# RTM_SFP_TOP.net
KiCad netlist of a schematic drawn in Altium Designer
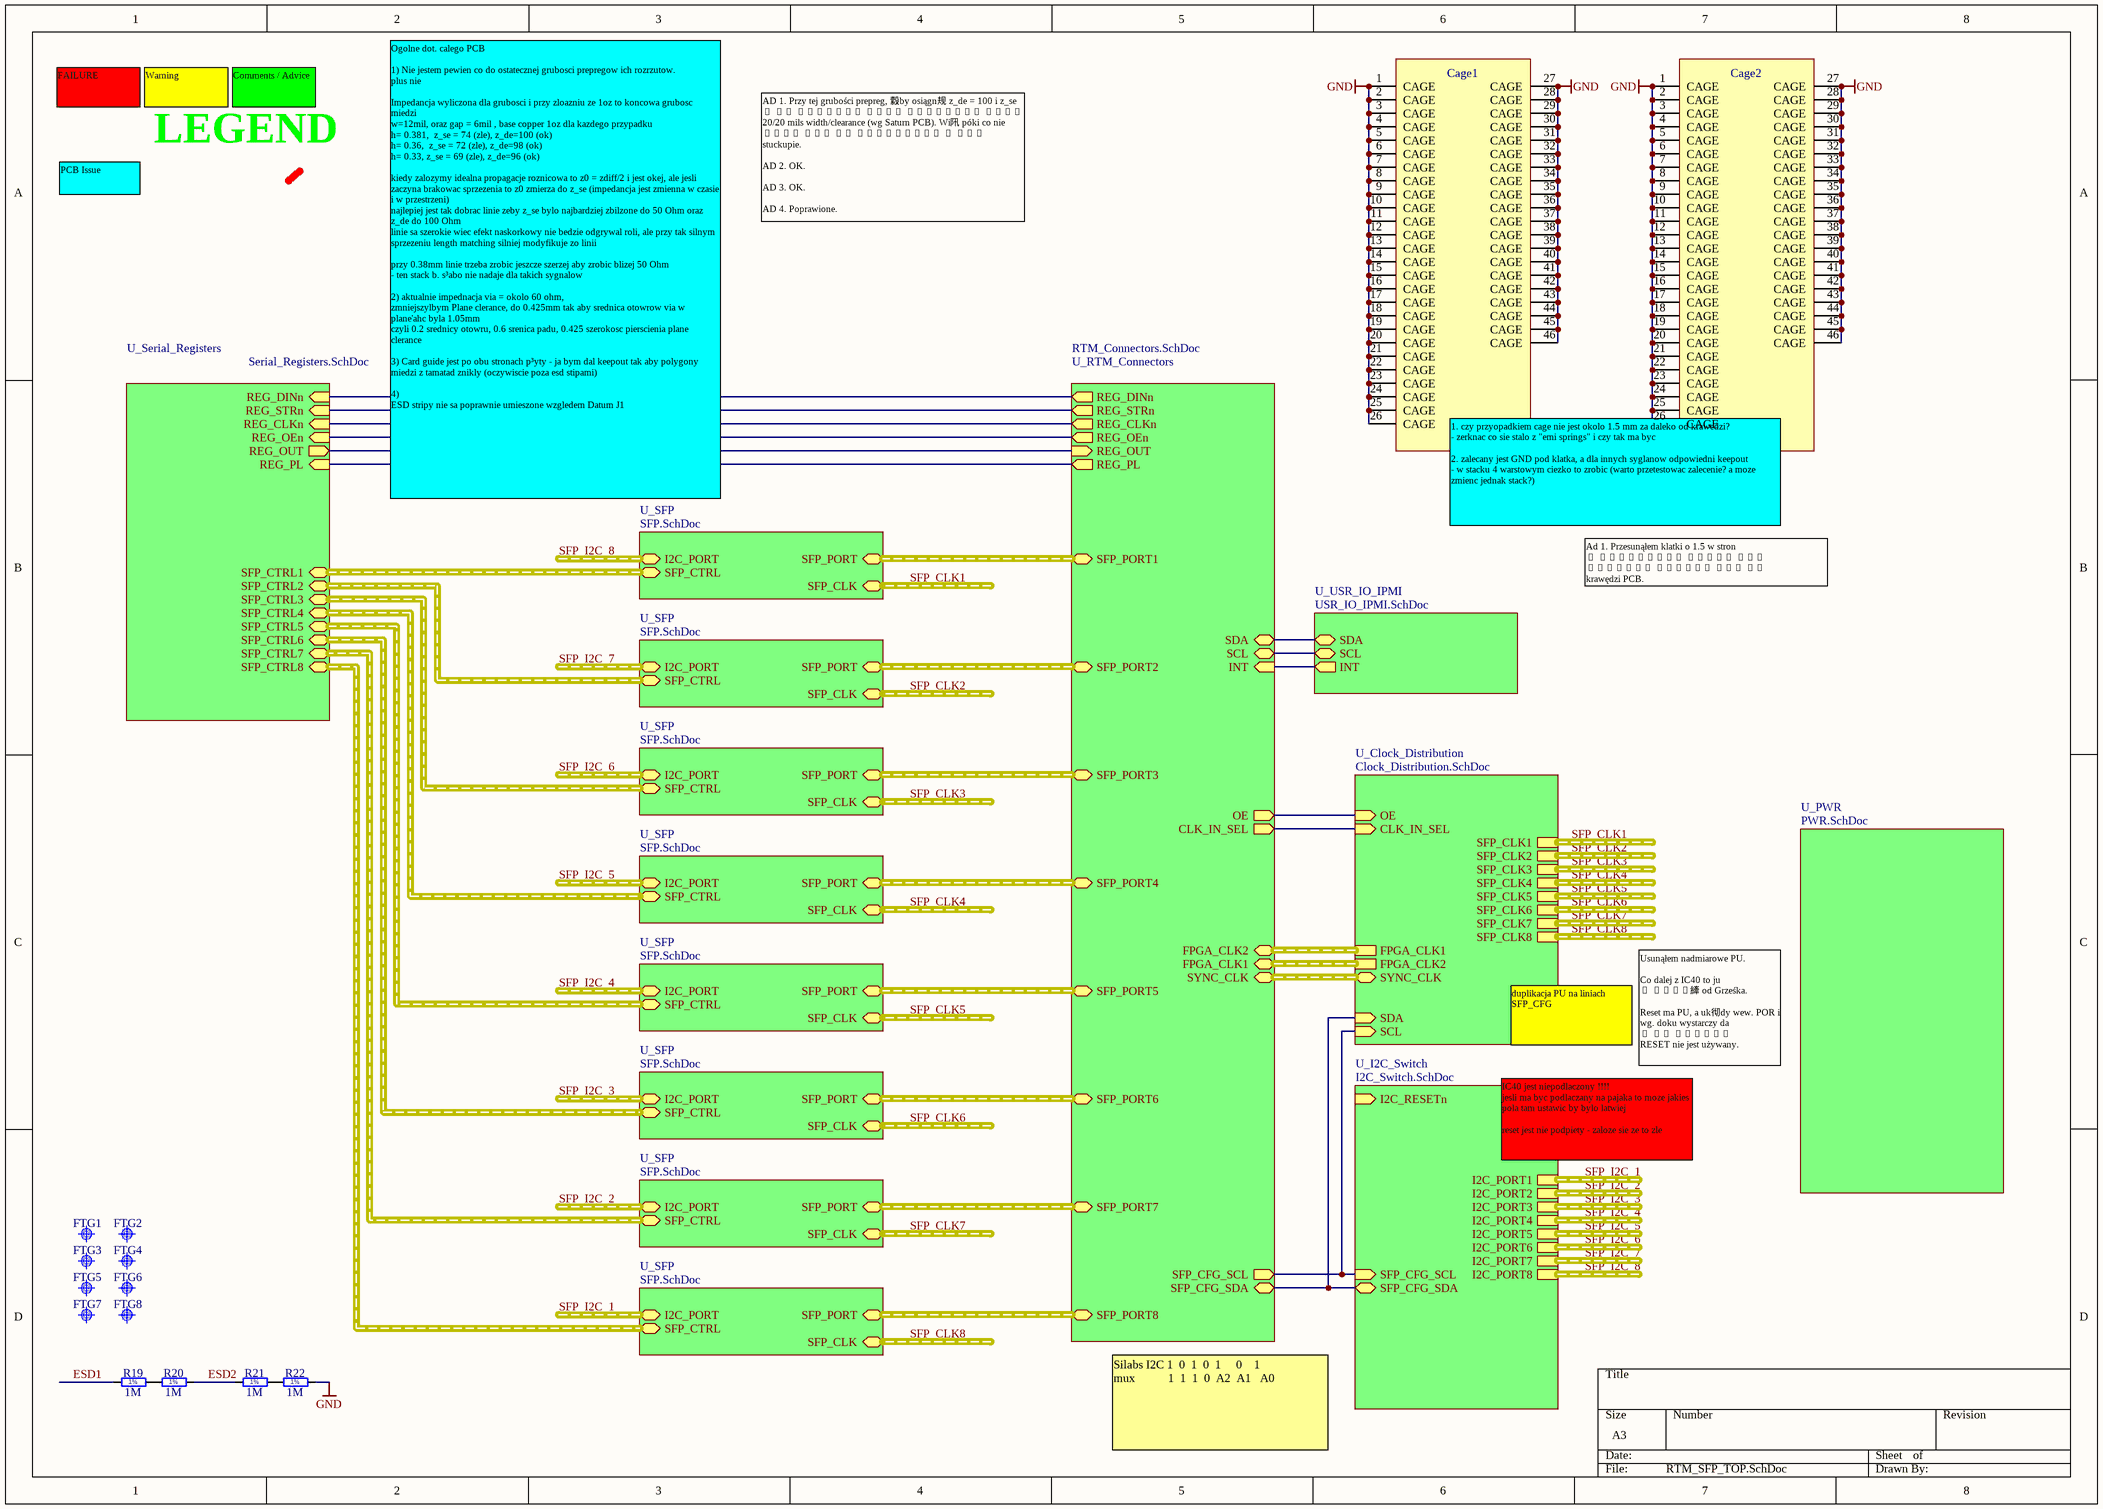
[diagram p0: RTM_SFP_TOP.SchDoc]

(export (version "E")
  (design (tool "Eeschema 10.0.6"))
  (components
    (comp (ref "Cage1")
      (value "SFP+")
      (footprint "TYCO_2007132-1")
      (description "SFP+  1x4 Cage (46 Pins)")
      (fields
        (field (name "PART NUMBER") "TYCO_2007132-1")
        (field (name "MANUFACTURER") "TYCO ELECTRONICS")
        (field (name "AUTHOR") "CERN DEM JLC")
      )
      (libsource (lib "Connectors") (part "SFP+ 1x4 Cage (46Pins)"))
    )
    (comp (ref "Cage2")
      (value "SFP+")
      (footprint "TYCO_2007132-1")
      (description "SFP+  1x4 Cage (46 Pins)")
      (fields
        (field (name "PART NUMBER") "TYCO_2007132-1")
        (field (name "MANUFACTURER") "TYCO ELECTRONICS")
        (field (name "AUTHOR") "CERN DEM JLC")
      )
      (libsource (lib "Connectors") (part "SFP+ 1x4 Cage (46Pins)"))
    )
    (comp (ref "FTG1")
      (value "Use only in PCB")
      (footprint "FIDUCIAL_TOP_S100-200")
      (description "Fiducial Target")
      (fields (field (name "PART NUMBER") "FIDUCIAL_TARGET_S100-200") (field (name "AUTHOR") "CERN DEM JLC"))
      (libsource (lib "Eletro-mechanical") (part "Fiducial Target"))
    )
    (comp (ref "FTG2")
      (value "Use only in PCB")
      (footprint "FIDUCIAL_TOP_C100-200")
      (description "Fiducial Target")
      (fields (field (name "PART NUMBER") "FIDUCIAL_TARGET_C100-200") (field (name "AUTHOR") "CERN DEM JLC"))
      (libsource (lib "Eletro-mechanical") (part "Fiducial Target"))
    )
    (comp (ref "FTG3")
      (value "Use only in PCB")
      (footprint "FIDUCIAL_TOP_S100-200")
      (description "Fiducial Target")
      (fields (field (name "PART NUMBER") "FIDUCIAL_TARGET_S100-200") (field (name "AUTHOR") "CERN DEM JLC"))
      (libsource (lib "Eletro-mechanical") (part "Fiducial Target"))
    )
    (comp (ref "FTG4")
      (value "Use only in PCB")
      (footprint "FIDUCIAL_TOP_C100-200")
      (description "Fiducial Target")
      (fields (field (name "PART NUMBER") "FIDUCIAL_TARGET_C100-200") (field (name "AUTHOR") "CERN DEM JLC"))
      (libsource (lib "Eletro-mechanical") (part "Fiducial Target"))
    )
    (comp (ref "FTG5")
      (value "Use only in PCB")
      (footprint "FIDUCIAL_TOP_S100-200")
      (description "Fiducial Target")
      (fields (field (name "PART NUMBER") "FIDUCIAL_TARGET_S100-200") (field (name "AUTHOR") "CERN DEM JLC"))
      (libsource (lib "Eletro-mechanical") (part "Fiducial Target"))
    )
    (comp (ref "FTG6")
      (value "Use only in PCB")
      (footprint "FIDUCIAL_TOP_C100-200")
      (description "Fiducial Target")
      (fields (field (name "PART NUMBER") "FIDUCIAL_TARGET_C100-200") (field (name "AUTHOR") "CERN DEM JLC"))
      (libsource (lib "Eletro-mechanical") (part "Fiducial Target"))
    )
    (comp (ref "FTG7")
      (value "Use only in PCB")
      (footprint "FIDUCIAL_TOP_S100-200")
      (description "Fiducial Target")
      (fields (field (name "PART NUMBER") "FIDUCIAL_TARGET_S100-200") (field (name "AUTHOR") "CERN DEM JLC"))
      (libsource (lib "Eletro-mechanical") (part "Fiducial Target"))
    )
    (comp (ref "FTG8")
      (value "Use only in PCB")
      (footprint "FIDUCIAL_TOP_C100-200")
      (description "Fiducial Target")
      (fields (field (name "PART NUMBER") "FIDUCIAL_TARGET_C100-200") (field (name "AUTHOR") "CERN DEM JLC"))
      (libsource (lib "Eletro-mechanical") (part "Fiducial Target"))
    )
    (comp (ref "R19")
      (value "1M")
      (footprint "RESC3216X65N")
      (description "Resistor - 1%")
      (fields
        (field (name "PART NUMBER") "R1206_1M_1%_0.25W_100PPM")
        (field (name "POWER") "0.25W")
        (field (name "AUTHOR") "CERN DEM JLC")
      )
      (libsource (lib "Resistors") (part "Resistor - 1%"))
    )
    (comp (ref "R20")
      (value "1M")
      (footprint "RESC3216X65N")
      (description "Resistor - 1%")
      (fields
        (field (name "PART NUMBER") "R1206_1M_1%_0.25W_100PPM")
        (field (name "POWER") "0.25W")
        (field (name "AUTHOR") "CERN DEM JLC")
      )
      (libsource (lib "Resistors") (part "Resistor - 1%"))
    )
    (comp (ref "R21")
      (value "1M")
      (footprint "RESC3216X65N")
      (description "Resistor - 1%")
      (fields
        (field (name "PART NUMBER") "R1206_1M_1%_0.25W_100PPM")
        (field (name "POWER") "0.25W")
        (field (name "AUTHOR") "CERN DEM JLC")
      )
      (libsource (lib "Resistors") (part "Resistor - 1%"))
    )
    (comp (ref "R22")
      (value "1M")
      (footprint "RESC3216X65N")
      (description "Resistor - 1%")
      (fields
        (field (name "PART NUMBER") "R1206_1M_1%_0.25W_100PPM")
        (field (name "POWER") "0.25W")
        (field (name "AUTHOR") "CERN DEM JLC")
      )
      (libsource (lib "Resistors") (part "Resistor - 1%"))
    )
  )
  (nets
    (net (code "18") (name "/ESD1") (class "Default")
      (node (ref "R19") (pin "1") (pinfunction "1_1") (pintype "passive"))
    )
    (net (code "19") (name "/ESD2") (class "Default")
      (node (ref "R20") (pin "2") (pinfunction "2_2") (pintype "passive"))
      (node (ref "R21") (pin "1") (pinfunction "1_1") (pintype "passive"))
    )
    (net (code "69") (name "GND") (class "Default")
      (node (ref "Cage1") (pin "1") (pinfunction "CAGE_1") (pintype "power_in"))
      (node (ref "Cage1") (pin "10") (pinfunction "CAGE_10") (pintype "power_in"))
      (node (ref "Cage1") (pin "11") (pinfunction "CAGE_11") (pintype "power_in"))
      (node (ref "Cage1") (pin "12") (pinfunction "CAGE_12") (pintype "power_in"))
      (node (ref "Cage1") (pin "13") (pinfunction "CAGE_13") (pintype "power_in"))
      (node (ref "Cage1") (pin "14") (pinfunction "CAGE_14") (pintype "power_in"))
      (node (ref "Cage1") (pin "15") (pinfunction "CAGE_15") (pintype "power_in"))
      (node (ref "Cage1") (pin "16") (pinfunction "CAGE_16") (pintype "power_in"))
      (node (ref "Cage1") (pin "17") (pinfunction "CAGE_17") (pintype "power_in"))
      (node (ref "Cage1") (pin "18") (pinfunction "CAGE_18") (pintype "power_in"))
      (node (ref "Cage1") (pin "19") (pinfunction "CAGE_19") (pintype "power_in"))
      (node (ref "Cage1") (pin "2") (pinfunction "CAGE_2") (pintype "power_in"))
      (node (ref "Cage1") (pin "20") (pinfunction "CAGE_20") (pintype "power_in"))
      (node (ref "Cage1") (pin "21") (pinfunction "CAGE_21") (pintype "power_in"))
      (node (ref "Cage1") (pin "22") (pinfunction "CAGE_22") (pintype "power_in"))
      (node (ref "Cage1") (pin "23") (pinfunction "CAGE_23") (pintype "power_in"))
      (node (ref "Cage1") (pin "24") (pinfunction "CAGE_24") (pintype "power_in"))
      (node (ref "Cage1") (pin "25") (pinfunction "CAGE_25") (pintype "power_in"))
      (node (ref "Cage1") (pin "26") (pinfunction "CAGE_26") (pintype "power_in"))
      (node (ref "Cage1") (pin "27") (pinfunction "CAGE_27") (pintype "power_in"))
      (node (ref "Cage1") (pin "28") (pinfunction "CAGE_28") (pintype "power_in"))
      (node (ref "Cage1") (pin "29") (pinfunction "CAGE_29") (pintype "power_in"))
      (node (ref "Cage1") (pin "3") (pinfunction "CAGE_3") (pintype "power_in"))
      (node (ref "Cage1") (pin "30") (pinfunction "CAGE_30") (pintype "power_in"))
      (node (ref "Cage1") (pin "31") (pinfunction "CAGE_31") (pintype "power_in"))
      (node (ref "Cage1") (pin "32") (pinfunction "CAGE_32") (pintype "power_in"))
      (node (ref "Cage1") (pin "33") (pinfunction "CAGE_33") (pintype "power_in"))
      (node (ref "Cage1") (pin "34") (pinfunction "CAGE_34") (pintype "power_in"))
      (node (ref "Cage1") (pin "35") (pinfunction "CAGE_35") (pintype "power_in"))
      (node (ref "Cage1") (pin "36") (pinfunction "CAGE_36") (pintype "power_in"))
      (node (ref "Cage1") (pin "37") (pinfunction "CAGE_37") (pintype "power_in"))
      (node (ref "Cage1") (pin "38") (pinfunction "CAGE_38") (pintype "power_in"))
      (node (ref "Cage1") (pin "39") (pinfunction "CAGE_39") (pintype "power_in"))
      (node (ref "Cage1") (pin "4") (pinfunction "CAGE_4") (pintype "power_in"))
      (node (ref "Cage1") (pin "40") (pinfunction "CAGE_40") (pintype "power_in"))
      (node (ref "Cage1") (pin "41") (pinfunction "CAGE_41") (pintype "power_in"))
      (node (ref "Cage1") (pin "42") (pinfunction "CAGE_42") (pintype "power_in"))
      (node (ref "Cage1") (pin "43") (pinfunction "CAGE_43") (pintype "power_in"))
      (node (ref "Cage1") (pin "44") (pinfunction "CAGE_44") (pintype "power_in"))
      (node (ref "Cage1") (pin "45") (pinfunction "CAGE_45") (pintype "power_in"))
      (node (ref "Cage1") (pin "46") (pinfunction "CAGE_46") (pintype "power_in"))
      (node (ref "Cage1") (pin "5") (pinfunction "CAGE_5") (pintype "power_in"))
      (node (ref "Cage1") (pin "6") (pinfunction "CAGE_6") (pintype "power_in"))
      (node (ref "Cage1") (pin "7") (pinfunction "CAGE_7") (pintype "power_in"))
      (node (ref "Cage1") (pin "8") (pinfunction "CAGE_8") (pintype "power_in"))
      (node (ref "Cage1") (pin "9") (pinfunction "CAGE_9") (pintype "power_in"))
      (node (ref "Cage2") (pin "1") (pinfunction "CAGE_1") (pintype "power_in"))
      (node (ref "Cage2") (pin "10") (pinfunction "CAGE_10") (pintype "power_in"))
      (node (ref "Cage2") (pin "11") (pinfunction "CAGE_11") (pintype "power_in"))
      (node (ref "Cage2") (pin "12") (pinfunction "CAGE_12") (pintype "power_in"))
      (node (ref "Cage2") (pin "13") (pinfunction "CAGE_13") (pintype "power_in"))
      (node (ref "Cage2") (pin "14") (pinfunction "CAGE_14") (pintype "power_in"))
      (node (ref "Cage2") (pin "15") (pinfunction "CAGE_15") (pintype "power_in"))
      (node (ref "Cage2") (pin "16") (pinfunction "CAGE_16") (pintype "power_in"))
      (node (ref "Cage2") (pin "17") (pinfunction "CAGE_17") (pintype "power_in"))
      (node (ref "Cage2") (pin "18") (pinfunction "CAGE_18") (pintype "power_in"))
      (node (ref "Cage2") (pin "19") (pinfunction "CAGE_19") (pintype "power_in"))
      (node (ref "Cage2") (pin "2") (pinfunction "CAGE_2") (pintype "power_in"))
      (node (ref "Cage2") (pin "20") (pinfunction "CAGE_20") (pintype "power_in"))
      (node (ref "Cage2") (pin "21") (pinfunction "CAGE_21") (pintype "power_in"))
      (node (ref "Cage2") (pin "22") (pinfunction "CAGE_22") (pintype "power_in"))
      (node (ref "Cage2") (pin "23") (pinfunction "CAGE_23") (pintype "power_in"))
      (node (ref "Cage2") (pin "24") (pinfunction "CAGE_24") (pintype "power_in"))
      (node (ref "Cage2") (pin "25") (pinfunction "CAGE_25") (pintype "power_in"))
      (node (ref "Cage2") (pin "26") (pinfunction "CAGE_26") (pintype "power_in"))
      (node (ref "Cage2") (pin "27") (pinfunction "CAGE_27") (pintype "power_in"))
      (node (ref "Cage2") (pin "28") (pinfunction "CAGE_28") (pintype "power_in"))
      (node (ref "Cage2") (pin "29") (pinfunction "CAGE_29") (pintype "power_in"))
      (node (ref "Cage2") (pin "3") (pinfunction "CAGE_3") (pintype "power_in"))
      (node (ref "Cage2") (pin "30") (pinfunction "CAGE_30") (pintype "power_in"))
      (node (ref "Cage2") (pin "31") (pinfunction "CAGE_31") (pintype "power_in"))
      (node (ref "Cage2") (pin "32") (pinfunction "CAGE_32") (pintype "power_in"))
      (node (ref "Cage2") (pin "33") (pinfunction "CAGE_33") (pintype "power_in"))
      (node (ref "Cage2") (pin "34") (pinfunction "CAGE_34") (pintype "power_in"))
      (node (ref "Cage2") (pin "35") (pinfunction "CAGE_35") (pintype "power_in"))
      (node (ref "Cage2") (pin "36") (pinfunction "CAGE_36") (pintype "power_in"))
      (node (ref "Cage2") (pin "37") (pinfunction "CAGE_37") (pintype "power_in"))
      (node (ref "Cage2") (pin "38") (pinfunction "CAGE_38") (pintype "power_in"))
      (node (ref "Cage2") (pin "39") (pinfunction "CAGE_39") (pintype "power_in"))
      (node (ref "Cage2") (pin "4") (pinfunction "CAGE_4") (pintype "power_in"))
      (node (ref "Cage2") (pin "40") (pinfunction "CAGE_40") (pintype "power_in"))
      (node (ref "Cage2") (pin "41") (pinfunction "CAGE_41") (pintype "power_in"))
      (node (ref "Cage2") (pin "42") (pinfunction "CAGE_42") (pintype "power_in"))
      (node (ref "Cage2") (pin "43") (pinfunction "CAGE_43") (pintype "power_in"))
      (node (ref "Cage2") (pin "44") (pinfunction "CAGE_44") (pintype "power_in"))
      (node (ref "Cage2") (pin "45") (pinfunction "CAGE_45") (pintype "power_in"))
      (node (ref "Cage2") (pin "46") (pinfunction "CAGE_46") (pintype "power_in"))
      (node (ref "Cage2") (pin "5") (pinfunction "CAGE_5") (pintype "power_in"))
      (node (ref "Cage2") (pin "6") (pinfunction "CAGE_6") (pintype "power_in"))
      (node (ref "Cage2") (pin "7") (pinfunction "CAGE_7") (pintype "power_in"))
      (node (ref "Cage2") (pin "8") (pinfunction "CAGE_8") (pintype "power_in"))
      (node (ref "Cage2") (pin "9") (pinfunction "CAGE_9") (pintype "power_in"))
      (node (ref "R22") (pin "2") (pinfunction "2_2") (pintype "passive"))
    )
    (net (code "70") (name "Net-(R19-Pad2)") (class "Default")
      (node (ref "R19") (pin "2") (pinfunction "2_2") (pintype "passive"))
      (node (ref "R20") (pin "1") (pinfunction "1_1") (pintype "passive"))
    )
    (net (code "71") (name "Net-(R21-Pad2)") (class "Default")
      (node (ref "R21") (pin "2") (pinfunction "2_2") (pintype "passive"))
      (node (ref "R22") (pin "1") (pinfunction "1_1") (pintype "passive"))
    )
  )
)
